# ProPrj_CH32V003-MAX4466_2025-10-29.net
KiCad netlist of a schematic drawn in EasyEDA Pro
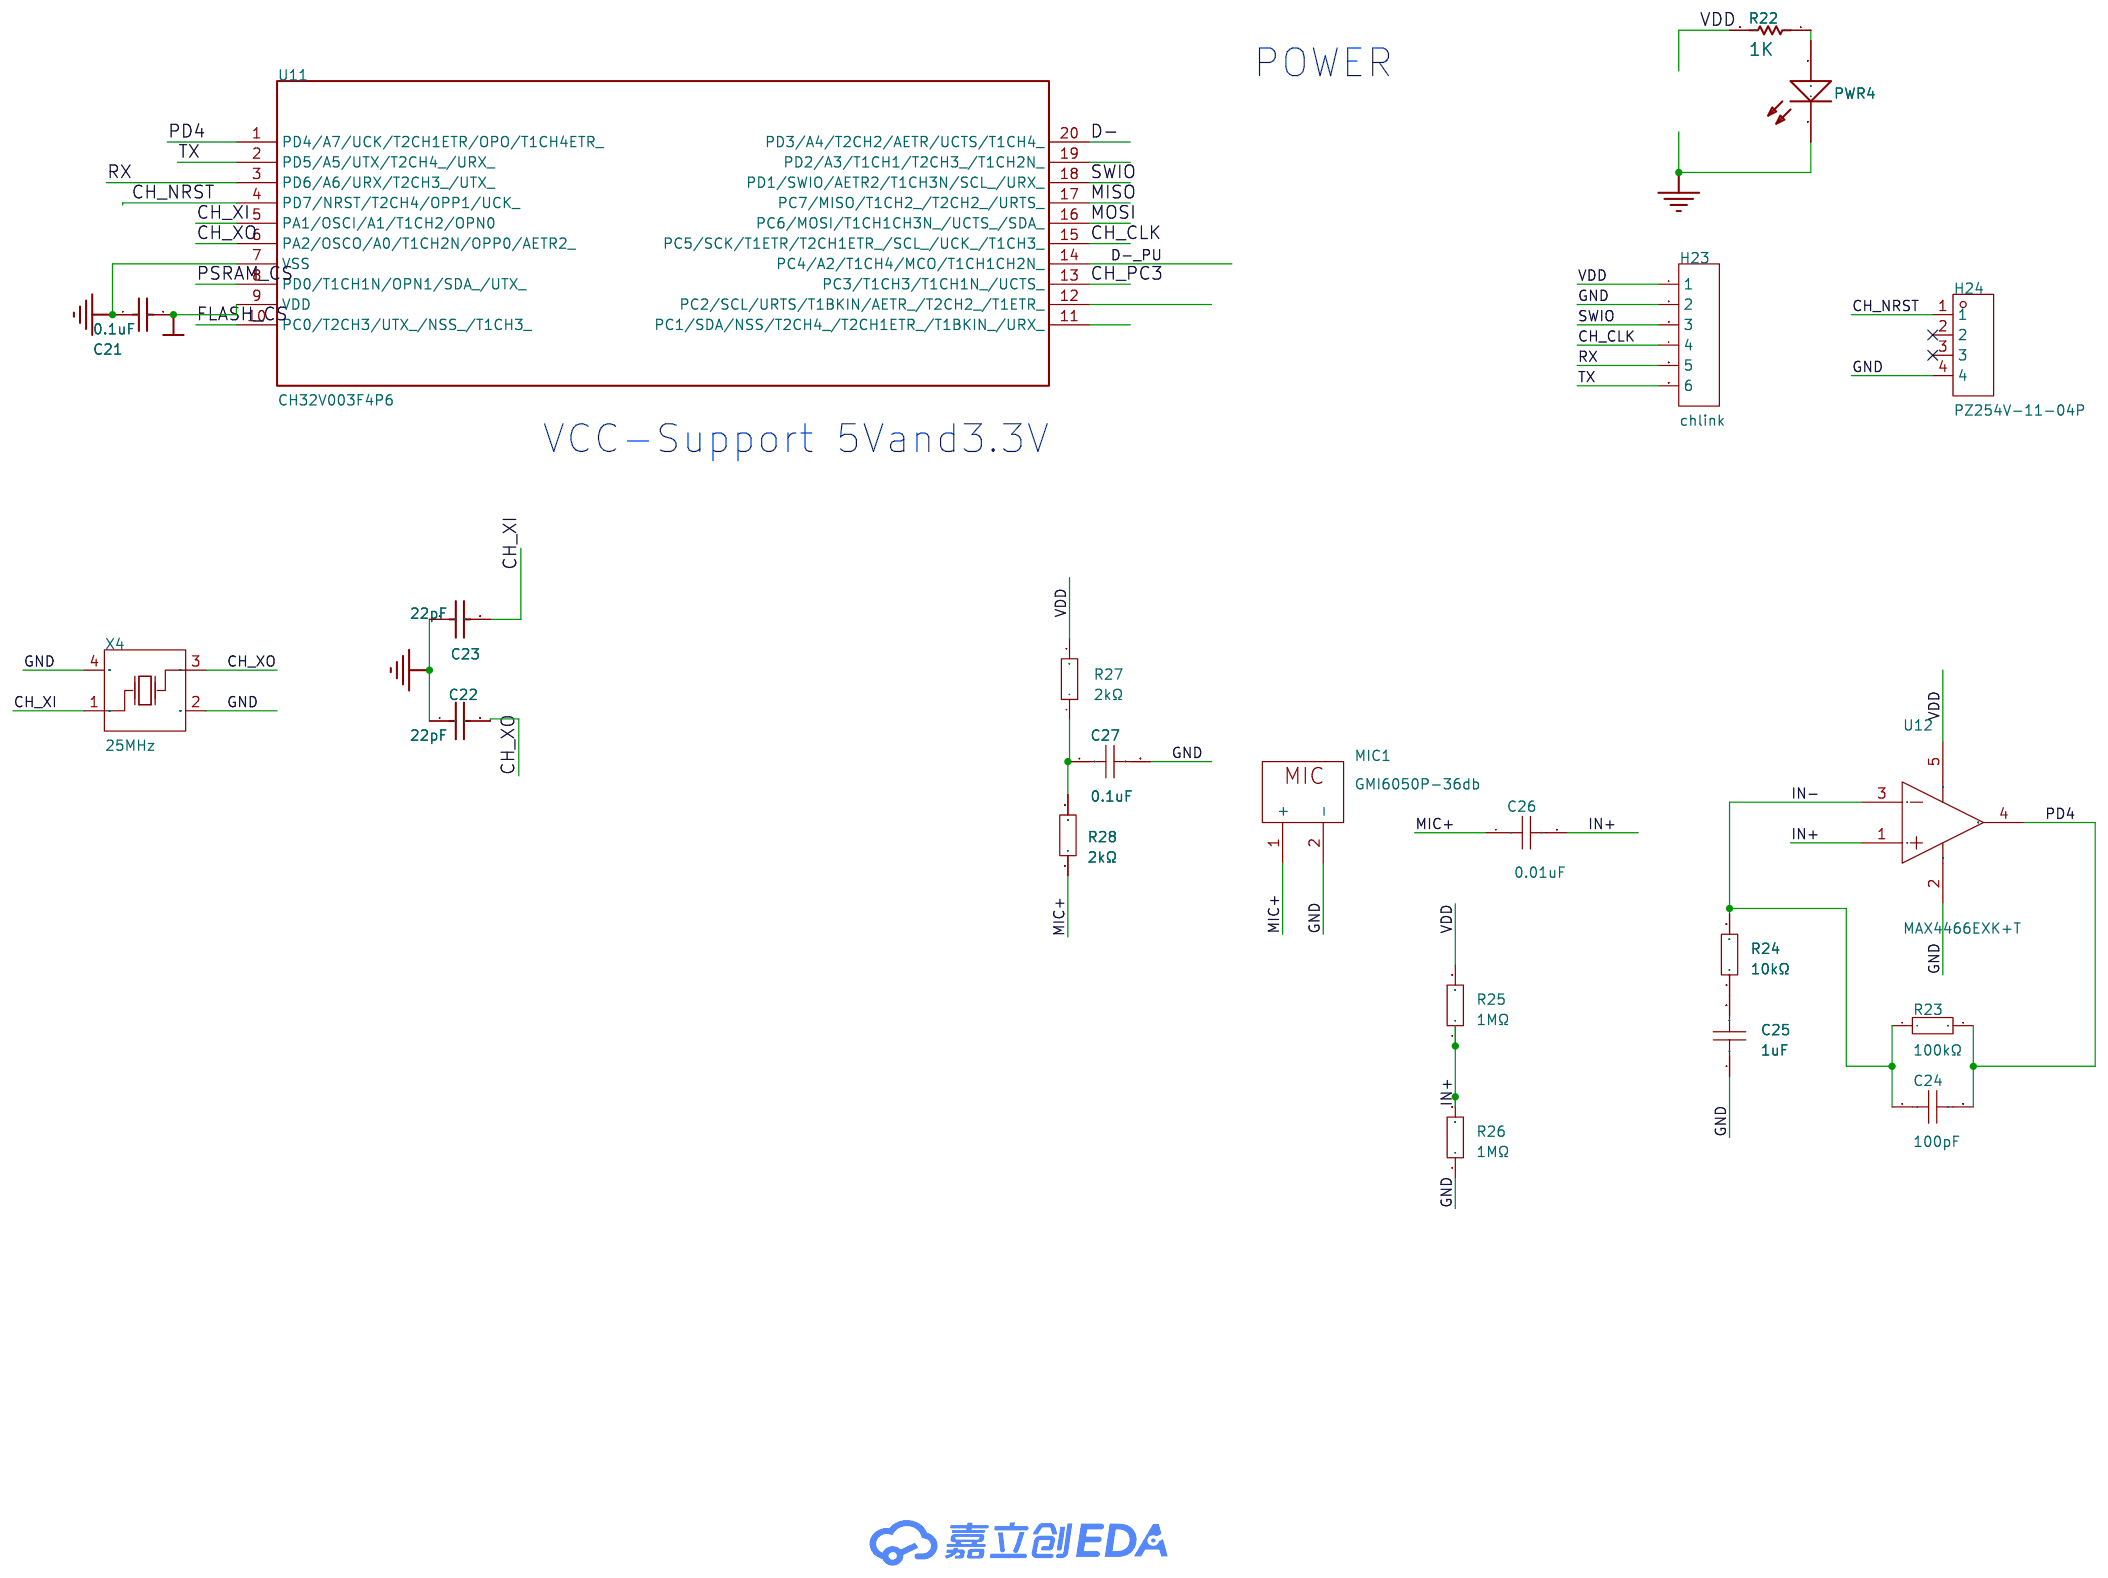
[diagram p0: schematic sheet]

(export (version "E")
  (design (tool "Eeschema 10.0.6"))
  (components
    (comp (ref "C21")
      (value "15pF")
      (footprint "easyedapro:0603_C")
      (description "Capacitor")
      (libsource (lib "easyedapro") (part "Cap"))
    )
    (comp (ref "C22")
      (value "22pF")
      (footprint "easyedapro:0603_C")
      (description "Capacitor")
      (libsource (lib "easyedapro") (part "CAP"))
    )
    (comp (ref "C23")
      (value "22pF")
      (footprint "easyedapro:0603_C")
      (description "Capacitor")
      (libsource (lib "easyedapro") (part "CAP"))
    )
    (comp (ref "C24")
      (value "100pF")
      (footprint "easyedapro:C0805")
      (description "容值:10uF;精度:±10%;额定电压:25V;温度系数:X5R;")
      (fields
        (field (name "Manufacturer Part") "CL21A106KAYNNNE")
        (field (name "Manufacturer") "SAMSUNG(三星)")
      )
      (libsource (lib "easyedapro") (part "CL21A106KAYNNNE"))
    )
    (comp (ref "C25")
      (value "1uF")
      (footprint "easyedapro:C0805")
      (description "容值:10uF;精度:±10%;额定电压:25V;温度系数:X5R;")
      (fields
        (field (name "Manufacturer Part") "CL21A106KAYNNNE")
        (field (name "Manufacturer") "SAMSUNG(三星)")
      )
      (libsource (lib "easyedapro") (part "CL21A106KAYNNNE"))
    )
    (comp (ref "C26")
      (value "0.01uF")
      (footprint "easyedapro:C0805")
      (description "容值:10uF;精度:±10%;额定电压:25V;温度系数:X5R;")
      (fields
        (field (name "Manufacturer Part") "CL21A106KAYNNNE")
        (field (name "Manufacturer") "SAMSUNG(三星)")
      )
      (libsource (lib "easyedapro") (part "CL21A106KAYNNNE"))
    )
    (comp (ref "C27")
      (value "0.1uF")
      (footprint "easyedapro:C0805")
      (description "容值:10uF;精度:±10%;额定电压:25V;温度系数:X5R;")
      (fields
        (field (name "Manufacturer Part") "CL21A106KAYNNNE")
        (field (name "Manufacturer") "SAMSUNG(三星)")
      )
      (libsource (lib "easyedapro") (part "CL21A106KAYNNNE"))
    )
    (comp (ref "H23")
      (value "chlink")
      (footprint "easyedapro:HDR-TH_6P-P2.54-V-M-1")
      (fields (field (name "Manufacturer") "BOOMELE(博穆精密)"))
      (libsource (lib "easyedapro") (part "Header-Male-2.54_1x6"))
    )
    (comp (ref "H24")
      (value "PZ254V-11-04P")
      (footprint "easyedapro:HDR-TH_4P-P2.54-V-M")
      (fields (field (name "Manufacturer") "XFCN(兴飞)"))
      (libsource (lib "easyedapro") (part "PZ254V-11-04P_C2691448"))
    )
    (comp (ref "MIC1")
      (value "GMI6050P-36db")
      (footprint "easyedapro:MIC-TH_BD6.0-P1.90-D0.4-L-FD_GMI6050P-2CXXDB")
      (fields (field (name "Manufacturer") "INGHAi(赢海)"))
      (libsource (lib "easyedapro") (part "GMI6050P-36DB"))
    )
    (comp (ref "PWR4")
      (value "POWER  red")
      (footprint "easyedapro:0603+")
      (description "Typical INFRARED GaAs LED")
      (libsource (lib "easyedapro") (part "LED0"))
    )
    (comp (ref "R22")
      (value "1K")
      (footprint "easyedapro:0603")
      (description "Semiconductor Resistor")
      (libsource (lib "easyedapro") (part "Res Semi"))
    )
    (comp (ref "R23")
      (value "100kΩ")
      (footprint "easyedapro:R0805")
      (description "电阻类型:厚膜电阻;阻值:10kΩ;精度:±1%;功率:125mW;工作电压:150V;温度系数:±100ppm/°C;")
      (fields
        (field (name "Manufacturer Part") "0805W8F1002T5E")
        (field (name "Manufacturer") "UNI-ROYAL(厚声)")
      )
      (libsource (lib "easyedapro") (part "0805W8F1002T5E"))
    )
    (comp (ref "R24")
      (value "10kΩ")
      (footprint "easyedapro:R0805")
      (description "电阻类型:厚膜电阻;阻值:10kΩ;精度:±1%;功率:125mW;工作电压:150V;温度系数:±100ppm/°C;")
      (fields
        (field (name "Manufacturer Part") "0805W8F1002T5E")
        (field (name "Manufacturer") "UNI-ROYAL(厚声)")
      )
      (libsource (lib "easyedapro") (part "0805W8F1002T5E"))
    )
    (comp (ref "R25")
      (value "1MΩ")
      (footprint "easyedapro:R0805")
      (description "电阻类型:厚膜电阻;阻值:10kΩ;精度:±1%;功率:125mW;工作电压:150V;温度系数:±100ppm/°C;")
      (fields
        (field (name "Manufacturer Part") "0805W8F1002T5E")
        (field (name "Manufacturer") "UNI-ROYAL(厚声)")
      )
      (libsource (lib "easyedapro") (part "0805W8F1002T5E"))
    )
    (comp (ref "R26")
      (value "1MΩ")
      (footprint "easyedapro:R0805")
      (description "电阻类型:厚膜电阻;阻值:10kΩ;精度:±1%;功率:125mW;工作电压:150V;温度系数:±100ppm/°C;")
      (fields
        (field (name "Manufacturer Part") "0805W8F1002T5E")
        (field (name "Manufacturer") "UNI-ROYAL(厚声)")
      )
      (libsource (lib "easyedapro") (part "0805W8F1002T5E"))
    )
    (comp (ref "R27")
      (value "2kΩ")
      (footprint "easyedapro:R0805")
      (description "电阻类型:厚膜电阻;阻值:10kΩ;精度:±1%;功率:125mW;工作电压:150V;温度系数:±100ppm/°C;")
      (fields
        (field (name "Manufacturer Part") "0805W8F1002T5E")
        (field (name "Manufacturer") "UNI-ROYAL(厚声)")
      )
      (libsource (lib "easyedapro") (part "0805W8F1002T5E"))
    )
    (comp (ref "R28")
      (value "2kΩ")
      (footprint "easyedapro:R0805")
      (description "电阻类型:厚膜电阻;阻值:10kΩ;精度:±1%;功率:125mW;工作电压:150V;温度系数:±100ppm/°C;")
      (fields
        (field (name "Manufacturer Part") "0805W8F1002T5E")
        (field (name "Manufacturer") "UNI-ROYAL(厚声)")
      )
      (libsource (lib "easyedapro") (part "0805W8F1002T5E"))
    )
    (comp (ref "U11")
      (value "CH32V003F4P6")
      (fields (field (name "Manufacturer") "WCH(南京沁恒)"))
      (libsource (lib "easyedapro") (part "CH32V003F4P6"))
    )
    (comp (ref "U12")
      (value "MAX4466EXK+T")
      (footprint "easyedapro:SC-70-5_L2.0-W1.3-P0.65-LS2.1-BR")
      (description "功放类型:-;扬声器通道数:单声道;输出功率:-;静态电流(Iq):-;")
      (fields (field (name "Manufacturer") "ADI(亚德诺)/MAXIM(美信)"))
      (libsource (lib "easyedapro") (part "MAX4466EXK+T"))
    )
    (comp (ref "X4")
      (value "25MHz")
      (footprint "easyedapro:CRYSTAL-SMD_4P-L3.2-W2.5-BL")
      (description "晶振类型:贴片晶振;频率:25MHz;常温频差:±10ppm;负载电容:12pF;频率稳定度:±20ppm;")
      (fields (field (name "Manufacturer Part") "X322525MOB4SI") (field (name "Manufacturer") "YXC(扬兴晶振)"))
      (libsource (lib "easyedapro") (part "X322525MOB4SI"))
    )
  )
  (nets
    (net (code "1") (name "/CH_CLK") (class "Default")
      (node (ref "H23") (pin "4") (pinfunction "4_4") (pintype "input"))
      (node (ref "U11") (pin "15") (pinfunction "PC5/SCK/T1ETR/T2CH1ETR_/SCL_/UCK_/T1CH3__15") (pintype "bidirectional"))
    )
    (net (code "2") (name "/CH_NRST") (class "Default")
      (node (ref "H24") (pin "1") (pinfunction "1_1") (pintype "unspecified"))
      (node (ref "U11") (pin "4") (pinfunction "PD7/NRST/T2CH4/OPP1/UCK__4") (pintype "bidirectional"))
    )
    (net (code "3") (name "/CH_PC3") (class "Default")
      (node (ref "U11") (pin "13") (pinfunction "PC3/T1CH3/T1CH1N_/UCTS__13") (pintype "bidirectional"))
    )
    (net (code "4") (name "/CH_XI") (class "Default")
      (node (ref "C23") (pin "2") (pinfunction "2_2") (pintype "unspecified"))
      (node (ref "U11") (pin "5") (pinfunction "PA1/OSCI/A1/T1CH2/OPN0_5") (pintype "bidirectional"))
      (node (ref "X4") (pin "1") (pinfunction "OSC1_1") (pintype "unspecified"))
    )
    (net (code "5") (name "/CH_XO") (class "Default")
      (node (ref "C22") (pin "2") (pinfunction "2_2") (pintype "unspecified"))
      (node (ref "U11") (pin "6") (pinfunction "PA2/OSCO/A0/T1CH2N/OPP0/AETR2__6") (pintype "bidirectional"))
      (node (ref "X4") (pin "3") (pinfunction "OSC2_3") (pintype "unspecified"))
    )
    (net (code "6") (name "/D-") (class "Default")
      (node (ref "U11") (pin "20") (pinfunction "PD3/A4/T2CH2/AETR/UCTS/T1CH4__20") (pintype "bidirectional"))
    )
    (net (code "7") (name "/D-_PU") (class "Default")
      (node (ref "U11") (pin "14") (pinfunction "PC4/A2/T1CH4/MCO/T1CH1CH2N__14") (pintype "bidirectional"))
    )
    (net (code "8") (name "/FLASH_CS") (class "Default")
      (node (ref "U11") (pin "10") (pinfunction "PC0/T2CH3/UTX_/NSS_/T1CH3__10") (pintype "bidirectional"))
    )
    (net (code "9") (name "/IN+") (class "Default")
      (node (ref "C26") (pin "2") (pinfunction "2_2") (pintype "unspecified"))
      (node (ref "R25") (pin "1") (pinfunction "1_1") (pintype "input"))
      (node (ref "R26") (pin "2") (pinfunction "2_2") (pintype "input"))
      (node (ref "U12") (pin "1") (pinfunction "IN+_1") (pintype "unspecified"))
    )
    (net (code "10") (name "/IN-") (class "Default")
      (node (ref "C24") (pin "1") (pinfunction "1_1") (pintype "unspecified"))
      (node (ref "R23") (pin "1") (pinfunction "1_1") (pintype "input"))
      (node (ref "R24") (pin "2") (pinfunction "2_2") (pintype "input"))
      (node (ref "U12") (pin "3") (pinfunction "IN-_3") (pintype "unspecified"))
    )
    (net (code "11") (name "/MIC+") (class "Default")
      (node (ref "C26") (pin "1") (pinfunction "1_1") (pintype "unspecified"))
      (node (ref "MIC1") (pin "1") (pinfunction "+_1") (pintype "unspecified"))
      (node (ref "R28") (pin "1") (pinfunction "1_1") (pintype "input"))
    )
    (net (code "12") (name "/MISO") (class "Default")
      (node (ref "U11") (pin "17") (pinfunction "PC7/MISO/T1CH2_/T2CH2_/URTS__17") (pintype "bidirectional"))
    )
    (net (code "13") (name "/MOSI") (class "Default")
      (node (ref "U11") (pin "16") (pinfunction "PC6/MOSI/T1CH1CH3N_/UCTS_/SDA__16") (pintype "bidirectional"))
    )
    (net (code "14") (name "/PD4") (class "Default")
      (node (ref "C24") (pin "2") (pinfunction "2_2") (pintype "unspecified"))
      (node (ref "R23") (pin "2") (pinfunction "2_2") (pintype "input"))
      (node (ref "U11") (pin "1") (pinfunction "PD4/A7/UCK/T2CH1ETR/OPO/T1CH4ETR__1") (pintype "bidirectional"))
      (node (ref "U12") (pin "4") (pinfunction "OUT_4") (pintype "output"))
    )
    (net (code "15") (name "/PSRAM_CS") (class "Default")
      (node (ref "U11") (pin "8") (pinfunction "PD0/T1CH1N/OPN1/SDA_/UTX__8") (pintype "bidirectional"))
    )
    (net (code "16") (name "/RX") (class "Default")
      (node (ref "H23") (pin "5") (pinfunction "5_5") (pintype "input"))
      (node (ref "U11") (pin "3") (pinfunction "PD6/A6/URX/T2CH3_/UTX__3") (pintype "bidirectional"))
    )
    (net (code "17") (name "/SWIO") (class "Default")
      (node (ref "H23") (pin "3") (pinfunction "3_3") (pintype "input"))
      (node (ref "U11") (pin "18") (pinfunction "PD1/SWIO/AETR2/T1CH3N/SCL_/URX__18") (pintype "bidirectional"))
    )
    (net (code "18") (name "/TX") (class "Default")
      (node (ref "H23") (pin "6") (pinfunction "6_6") (pintype "input"))
      (node (ref "U11") (pin "2") (pinfunction "PD5/A5/UTX/T2CH4_/URX__2") (pintype "bidirectional"))
    )
    (net (code "19") (name "GND") (class "Default")
      (node (ref "C21") (pin "1") (pinfunction "1_1") (pintype "unspecified"))
      (node (ref "C22") (pin "1") (pinfunction "1_1") (pintype "unspecified"))
      (node (ref "C23") (pin "1") (pinfunction "1_1") (pintype "unspecified"))
      (node (ref "C25") (pin "1") (pinfunction "1_1") (pintype "unspecified"))
      (node (ref "C27") (pin "2") (pinfunction "2_2") (pintype "unspecified"))
      (node (ref "H23") (pin "2") (pinfunction "2_2") (pintype "input"))
      (node (ref "H24") (pin "4") (pinfunction "4_4") (pintype "unspecified"))
      (node (ref "MIC1") (pin "2") (pinfunction "-_2") (pintype "unspecified"))
      (node (ref "PWR4") (pin "2") (pinfunction "K_2") (pintype "unspecified"))
      (node (ref "R26") (pin "1") (pinfunction "1_1") (pintype "input"))
      (node (ref "U11") (pin "7") (pinfunction "VSS_7") (pintype "unspecified"))
      (node (ref "U12") (pin "2") (pinfunction "GND_2") (pintype "unspecified"))
      (node (ref "X4") (pin "2") (pinfunction "GND_2") (pintype "unspecified"))
      (node (ref "X4") (pin "4") (pinfunction "GND_4") (pintype "unspecified"))
    )
    (net (code "20") (name "Net-(C25-Pad2)") (class "Default")
      (node (ref "C25") (pin "2") (pinfunction "2_2") (pintype "unspecified"))
      (node (ref "R24") (pin "1") (pinfunction "1_1") (pintype "input"))
    )
    (net (code "21") (name "Net-(C27-Pad1)") (class "Default")
      (node (ref "C27") (pin "1") (pinfunction "1_1") (pintype "unspecified"))
      (node (ref "R27") (pin "1") (pinfunction "1_1") (pintype "input"))
      (node (ref "R28") (pin "2") (pinfunction "2_2") (pintype "input"))
    )
    (net (code "22") (name "Net-(PWR4-A)") (class "Default")
      (node (ref "PWR4") (pin "1") (pinfunction "A_1") (pintype "unspecified"))
      (node (ref "R22") (pin "1") (pinfunction "1_1") (pintype "unspecified"))
    )
    (net (code "23") (name "VDD") (class "Default")
      (node (ref "C21") (pin "2") (pinfunction "2_2") (pintype "unspecified"))
      (node (ref "H23") (pin "1") (pinfunction "1_1") (pintype "input"))
      (node (ref "R22") (pin "2") (pinfunction "2_2") (pintype "unspecified"))
      (node (ref "R25") (pin "2") (pinfunction "2_2") (pintype "input"))
      (node (ref "R27") (pin "2") (pinfunction "2_2") (pintype "input"))
      (node (ref "U11") (pin "9") (pinfunction "VDD_9") (pintype "unspecified"))
      (node (ref "U12") (pin "5") (pinfunction "VCC_5") (pintype "unspecified"))
    )
    (net (code "24") (name "unconnected-(H24-Pad2)") (class "Default")
      (node (ref "H24") (pin "2") (pinfunction "2_2") (pintype "unspecified+no_connect"))
    )
    (net (code "25") (name "unconnected-(H24-Pad3)") (class "Default")
      (node (ref "H24") (pin "3") (pinfunction "3_3") (pintype "unspecified+no_connect"))
    )
    (net (code "26") (name "unconnected-(U11-PC1{slash}SDA{slash}NSS{slash}T2CH4_{slash}T2CH1ETR_{slash}T1BKIN_{slash}URX_-Pad11)") (class "Default")
      (node (ref "U11") (pin "11") (pinfunction "PC1/SDA/NSS/T2CH4_/T2CH1ETR_/T1BKIN_/URX__11") (pintype "bidirectional"))
    )
    (net (code "27") (name "unconnected-(U11-PC2{slash}SCL{slash}URTS{slash}T1BKIN{slash}AETR_{slash}T2CH2_{slash}T1ETR_-Pad12)") (class "Default")
      (node (ref "U11") (pin "12") (pinfunction "PC2/SCL/URTS/T1BKIN/AETR_/T2CH2_/T1ETR__12") (pintype "bidirectional"))
    )
    (net (code "28") (name "unconnected-(U11-PD2{slash}A3{slash}T1CH1{slash}T2CH3_{slash}T1CH2N_-Pad19)") (class "Default")
      (node (ref "U11") (pin "19") (pinfunction "PD2/A3/T1CH1/T2CH3_/T1CH2N__19") (pintype "bidirectional"))
    )
  )
)
